# Sheet1.net
KiCad netlist of a schematic drawn in Altium Designer
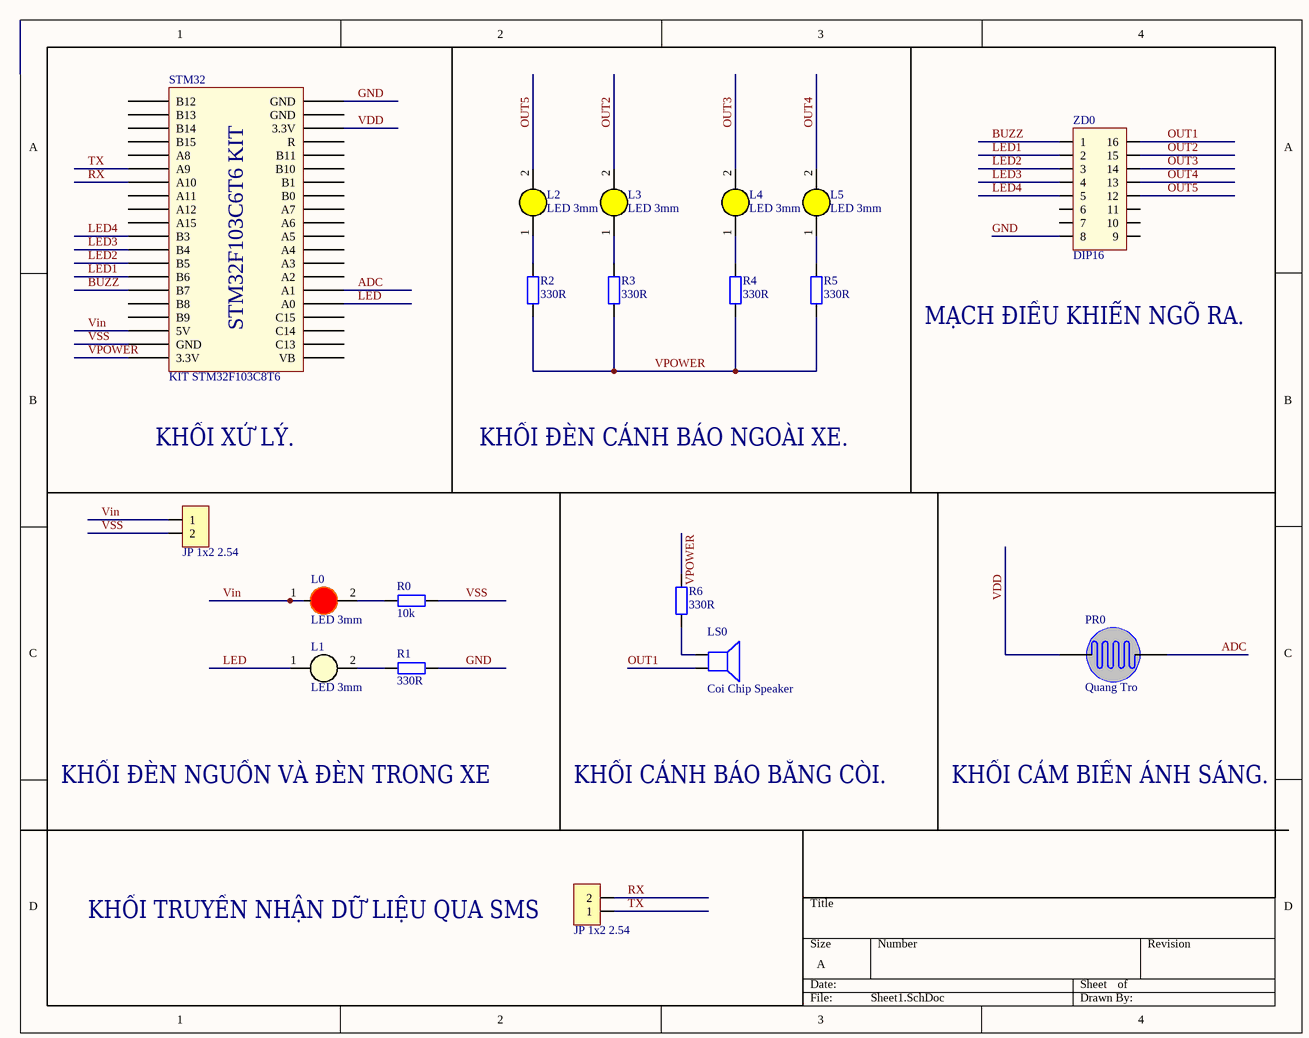
[diagram p0: Sheet1.SchDoc]

(export (version "E")
  (design (tool "Eeschema 10.0.6"))
  (components
    (comp (ref "JP1")
      (value "JP 1x2 2.54")
      (footprint "JP 1x2 DT")
      (description "Cắm")
      (libsource (lib "Altium_Lib_by_KhueNguyenCreator") (part "JP 1x2 2.54 Duc Thang"))
    )
    (comp (ref "JP2")
      (value "JP 1x2 2.54")
      (footprint "JP 1x2 CT")
      (description "Cắm")
      (libsource (lib "Altium_Lib_by_KhueNguyenCreator") (part "JP 1x2 2.54 Cai Thang"))
    )
    (comp (ref "L0")
      (value "LED 3mm")
      (footprint "LED-3MM-RED")
      (description "Cắm")
      (libsource (lib "Altium_Lib_by_KhueNguyenCreator") (part "LED 3mm Do"))
    )
    (comp (ref "L1")
      (value "LED 3mm")
      (footprint "LED-3MM-WHITE")
      (description "Cắm")
      (libsource (lib "Altium_Lib_by_KhueNguyenCreator") (part "LED 3mm Trang"))
    )
    (comp (ref "L2")
      (value "LED 3mm")
      (footprint "LED-3MM-YELLOW")
      (description "Cắm")
      (libsource (lib "Altium_Lib_by_KhueNguyenCreator") (part "LED 3mm Vang"))
    )
    (comp (ref "L3")
      (value "LED 3mm")
      (footprint "LED-3MM-YELLOW")
      (description "Cắm")
      (libsource (lib "Altium_Lib_by_KhueNguyenCreator") (part "LED 3mm Vang"))
    )
    (comp (ref "L4")
      (value "LED 3mm")
      (footprint "LED-3MM-YELLOW")
      (description "Cắm")
      (libsource (lib "Altium_Lib_by_KhueNguyenCreator") (part "LED 3mm Vang"))
    )
    (comp (ref "L5")
      (value "LED 3mm")
      (footprint "LED-3MM-YELLOW")
      (description "Cắm")
      (libsource (lib "Altium_Lib_by_KhueNguyenCreator") (part "LED 3mm Vang"))
    )
    (comp (ref "LS0")
      (value "Coi Chip Speaker")
      (footprint "Coi Chip Speacker")
      (description "Còi chip")
      (libsource (lib "Altium_Lib_by_KhueNguyenCreator") (part "Coi Chip Speaker"))
    )
    (comp (ref "PR0")
      (value "Quang Tro")
      (footprint "Quang Tro")
      (description "Photoresistor")
      (fields (field (name "CREATOR") "Bien Nguyen"))
      (libsource (lib "Altium_Lib_by_KhueNguyenCreator") (part "Quang Tro"))
    )
    (comp (ref "R0")
      (value "10k")
      (footprint "tro vach 1/4w")
      (description "Căm")
      (libsource (lib "Altium_Lib_by_KhueNguyenCreator") (part "Tro Vach 1/4W 5% 10k"))
    )
    (comp (ref "R1")
      (value "330R")
      (footprint "tro vach 1/4w")
      (description "Cắm")
      (libsource (lib "Altium_Lib_by_KhueNguyenCreator") (part "Tro Vach 1/4W 5% 330R"))
    )
    (comp (ref "R2")
      (value "330R")
      (footprint "tro vach 1/4w")
      (description "Cắm")
      (libsource (lib "Altium_Lib_by_KhueNguyenCreator") (part "Tro Vach 1/4W 5% 330R"))
    )
    (comp (ref "R3")
      (value "330R")
      (footprint "tro vach 1/4w")
      (description "Cắm")
      (libsource (lib "Altium_Lib_by_KhueNguyenCreator") (part "Tro Vach 1/4W 5% 330R"))
    )
    (comp (ref "R4")
      (value "330R")
      (footprint "tro vach 1/4w")
      (description "Cắm")
      (libsource (lib "Altium_Lib_by_KhueNguyenCreator") (part "Tro Vach 1/4W 5% 330R"))
    )
    (comp (ref "R5")
      (value "330R")
      (footprint "tro vach 1/4w")
      (description "Cắm")
      (libsource (lib "Altium_Lib_by_KhueNguyenCreator") (part "Tro Vach 1/4W 5% 330R"))
    )
    (comp (ref "R6")
      (value "330R")
      (footprint "tro vach 1/4w")
      (description "Cắm")
      (libsource (lib "Altium_Lib_by_KhueNguyenCreator") (part "Tro Vach 1/4W 5% 330R"))
    )
    (comp (ref "STM32")
      (value "KIT STM32F103C8T6")
      (footprint "STM32F103 KIT")
      (description "KIT STM32F103C8T6 Bluepill")
      (libsource (lib "Altium_Lib_by_KhueNguyenCreator") (part "STM32f103 Bluepill"))
    )
    (comp (ref "ZD0") (value "DIP16") (footprint "DIP16/W0.3") (libsource (lib "syhaunguyen") (part "DIP16")))
  )
  (nets
    (net (code "1") (name "/ADC") (class "Default")
      (node (ref "PR0") (pin "2") (pinfunction "2_2") (pintype "passive"))
      (node (ref "STM32") (pin "26") (pinfunction "A1_26") (pintype "passive"))
    )
    (net (code "2") (name "/BUZZ") (class "Default")
      (node (ref "STM32") (pin "15") (pinfunction "B7_15") (pintype "passive"))
      (node (ref "ZD0") (pin "1") (pinfunction "1_1") (pintype "passive"))
    )
    (net (code "3") (name "/GND") (class "Default")
      (node (ref "R1") (pin "1") (pinfunction "1_1") (pintype "passive"))
      (node (ref "STM32") (pin "40") (pinfunction "GND_40") (pintype "passive"))
      (node (ref "ZD0") (pin "8") (pinfunction "8_8") (pintype "passive"))
    )
    (net (code "4") (name "/LED") (class "Default")
      (node (ref "L1") (pin "1") (pinfunction "A_1") (pintype "passive"))
      (node (ref "STM32") (pin "25") (pinfunction "A0_25") (pintype "passive"))
    )
    (net (code "5") (name "/LED1") (class "Default")
      (node (ref "STM32") (pin "14") (pinfunction "B6_14") (pintype "passive"))
      (node (ref "ZD0") (pin "2") (pinfunction "2_2") (pintype "passive"))
    )
    (net (code "6") (name "/LED2") (class "Default")
      (node (ref "STM32") (pin "13") (pinfunction "B5_13") (pintype "passive"))
      (node (ref "ZD0") (pin "3") (pinfunction "3_3") (pintype "passive"))
    )
    (net (code "7") (name "/LED3") (class "Default")
      (node (ref "STM32") (pin "12") (pinfunction "B4_12") (pintype "passive"))
      (node (ref "ZD0") (pin "4") (pinfunction "4_4") (pintype "passive"))
    )
    (net (code "8") (name "/LED4") (class "Default")
      (node (ref "STM32") (pin "11") (pinfunction "B3_11") (pintype "passive"))
      (node (ref "ZD0") (pin "5") (pinfunction "5_5") (pintype "passive"))
    )
    (net (code "9") (name "/OUT1") (class "Default")
      (node (ref "LS0") (pin "2") (pinfunction "2_2") (pintype "passive"))
      (node (ref "ZD0") (pin "16") (pinfunction "16_16") (pintype "passive"))
    )
    (net (code "10") (name "/OUT2") (class "Default")
      (node (ref "L3") (pin "2") (pinfunction "K_2") (pintype "passive"))
      (node (ref "ZD0") (pin "15") (pinfunction "15_15") (pintype "passive"))
    )
    (net (code "11") (name "/OUT3") (class "Default")
      (node (ref "L4") (pin "2") (pinfunction "K_2") (pintype "passive"))
      (node (ref "ZD0") (pin "14") (pinfunction "14_14") (pintype "passive"))
    )
    (net (code "12") (name "/OUT4") (class "Default")
      (node (ref "L5") (pin "2") (pinfunction "K_2") (pintype "passive"))
      (node (ref "ZD0") (pin "13") (pinfunction "13_13") (pintype "passive"))
    )
    (net (code "13") (name "/OUT5") (class "Default")
      (node (ref "L2") (pin "2") (pinfunction "K_2") (pintype "passive"))
      (node (ref "ZD0") (pin "12") (pinfunction "12_12") (pintype "passive"))
    )
    (net (code "14") (name "/RX") (class "Default")
      (node (ref "JP2") (pin "2") (pinfunction "2_2") (pintype "passive"))
      (node (ref "STM32") (pin "7") (pinfunction "A10_7") (pintype "passive"))
    )
    (net (code "15") (name "/TX") (class "Default")
      (node (ref "JP2") (pin "1") (pinfunction "1_1") (pintype "passive"))
      (node (ref "STM32") (pin "6") (pinfunction "A9_6") (pintype "passive"))
    )
    (net (code "16") (name "/VDD") (class "Default")
      (node (ref "PR0") (pin "1") (pinfunction "1_1") (pintype "passive"))
      (node (ref "STM32") (pin "38") (pinfunction "3.3V_38") (pintype "passive"))
    )
    (net (code "17") (name "/VPOWER") (class "Default")
      (node (ref "R2") (pin "1") (pinfunction "1_1") (pintype "passive"))
      (node (ref "R3") (pin "1") (pinfunction "1_1") (pintype "passive"))
      (node (ref "R4") (pin "1") (pinfunction "1_1") (pintype "passive"))
      (node (ref "R5") (pin "1") (pinfunction "1_1") (pintype "passive"))
      (node (ref "R6") (pin "2") (pinfunction "2_2") (pintype "passive"))
      (node (ref "STM32") (pin "20") (pinfunction "3.3V_20") (pintype "passive"))
    )
    (net (code "18") (name "/VSS") (class "Default")
      (node (ref "JP1") (pin "2") (pinfunction "2_2") (pintype "passive"))
      (node (ref "R0") (pin "2") (pinfunction "2_2") (pintype "passive"))
      (node (ref "STM32") (pin "19") (pinfunction "GND_19") (pintype "passive"))
    )
    (net (code "19") (name "/Vin") (class "Default")
      (node (ref "JP1") (pin "1") (pinfunction "1_1") (pintype "passive"))
      (node (ref "L0") (pin "1") (pinfunction "A_1") (pintype "passive"))
      (node (ref "STM32") (pin "18") (pinfunction "5V_18") (pintype "passive"))
    )
    (net (code "20") (name "Net-(L0-K)") (class "Default")
      (node (ref "L0") (pin "2") (pinfunction "K_2") (pintype "passive"))
      (node (ref "R0") (pin "1") (pinfunction "1_1") (pintype "passive"))
    )
    (net (code "21") (name "Net-(L1-K)") (class "Default")
      (node (ref "L1") (pin "2") (pinfunction "K_2") (pintype "passive"))
      (node (ref "R1") (pin "2") (pinfunction "2_2") (pintype "passive"))
    )
    (net (code "22") (name "Net-(L2-A)") (class "Default")
      (node (ref "L2") (pin "1") (pinfunction "A_1") (pintype "passive"))
      (node (ref "R2") (pin "2") (pinfunction "2_2") (pintype "passive"))
    )
    (net (code "23") (name "Net-(L3-A)") (class "Default")
      (node (ref "L3") (pin "1") (pinfunction "A_1") (pintype "passive"))
      (node (ref "R3") (pin "2") (pinfunction "2_2") (pintype "passive"))
    )
    (net (code "24") (name "Net-(L4-A)") (class "Default")
      (node (ref "L4") (pin "1") (pinfunction "A_1") (pintype "passive"))
      (node (ref "R4") (pin "2") (pinfunction "2_2") (pintype "passive"))
    )
    (net (code "25") (name "Net-(L5-A)") (class "Default")
      (node (ref "L5") (pin "1") (pinfunction "A_1") (pintype "passive"))
      (node (ref "R5") (pin "2") (pinfunction "2_2") (pintype "passive"))
    )
    (net (code "26") (name "Net-(LS0-Pad1)") (class "Default")
      (node (ref "LS0") (pin "1") (pinfunction "1_1") (pintype "passive"))
      (node (ref "R6") (pin "1") (pinfunction "1_1") (pintype "passive"))
    )
    (net (code "27") (name "unconnected-(STM32-A2-Pad27)") (class "Default")
      (node (ref "STM32") (pin "27") (pinfunction "A2_27") (pintype "passive"))
    )
    (net (code "28") (name "unconnected-(STM32-A3-Pad28)") (class "Default")
      (node (ref "STM32") (pin "28") (pinfunction "A3_28") (pintype "passive"))
    )
    (net (code "29") (name "unconnected-(STM32-A4-Pad29)") (class "Default")
      (node (ref "STM32") (pin "29") (pinfunction "A4_29") (pintype "passive"))
    )
    (net (code "30") (name "unconnected-(STM32-A5-Pad30)") (class "Default")
      (node (ref "STM32") (pin "30") (pinfunction "A5_30") (pintype "passive"))
    )
    (net (code "31") (name "unconnected-(STM32-A6-Pad31)") (class "Default")
      (node (ref "STM32") (pin "31") (pinfunction "A6_31") (pintype "passive"))
    )
    (net (code "32") (name "unconnected-(STM32-A7-Pad32)") (class "Default")
      (node (ref "STM32") (pin "32") (pinfunction "A7_32") (pintype "passive"))
    )
    (net (code "33") (name "unconnected-(STM32-A8-Pad5)") (class "Default")
      (node (ref "STM32") (pin "5") (pinfunction "A8_5") (pintype "passive"))
    )
    (net (code "34") (name "unconnected-(STM32-A11-Pad8)") (class "Default")
      (node (ref "STM32") (pin "8") (pinfunction "A11_8") (pintype "passive"))
    )
    (net (code "35") (name "unconnected-(STM32-A12-Pad9)") (class "Default")
      (node (ref "STM32") (pin "9") (pinfunction "A12_9") (pintype "passive"))
    )
    (net (code "36") (name "unconnected-(STM32-A15-Pad10)") (class "Default")
      (node (ref "STM32") (pin "10") (pinfunction "A15_10") (pintype "passive"))
    )
    (net (code "37") (name "unconnected-(STM32-B0-Pad33)") (class "Default")
      (node (ref "STM32") (pin "33") (pinfunction "B0_33") (pintype "passive"))
    )
    (net (code "38") (name "unconnected-(STM32-B1-Pad34)") (class "Default")
      (node (ref "STM32") (pin "34") (pinfunction "B1_34") (pintype "passive"))
    )
    (net (code "39") (name "unconnected-(STM32-B8-Pad16)") (class "Default")
      (node (ref "STM32") (pin "16") (pinfunction "B8_16") (pintype "passive"))
    )
    (net (code "40") (name "unconnected-(STM32-B9-Pad17)") (class "Default")
      (node (ref "STM32") (pin "17") (pinfunction "B9_17") (pintype "passive"))
    )
    (net (code "41") (name "unconnected-(STM32-B10-Pad35)") (class "Default")
      (node (ref "STM32") (pin "35") (pinfunction "B10_35") (pintype "passive"))
    )
    (net (code "42") (name "unconnected-(STM32-B11-Pad36)") (class "Default")
      (node (ref "STM32") (pin "36") (pinfunction "B11_36") (pintype "passive"))
    )
    (net (code "43") (name "unconnected-(STM32-B12-Pad1)") (class "Default")
      (node (ref "STM32") (pin "1") (pinfunction "B12_1") (pintype "passive"))
    )
    (net (code "44") (name "unconnected-(STM32-B13-Pad2)") (class "Default")
      (node (ref "STM32") (pin "2") (pinfunction "B13_2") (pintype "passive"))
    )
    (net (code "45") (name "unconnected-(STM32-B14-Pad3)") (class "Default")
      (node (ref "STM32") (pin "3") (pinfunction "B14_3") (pintype "passive"))
    )
    (net (code "46") (name "unconnected-(STM32-B15-Pad4)") (class "Default")
      (node (ref "STM32") (pin "4") (pinfunction "B15_4") (pintype "passive"))
    )
    (net (code "47") (name "unconnected-(STM32-C13-Pad22)") (class "Default")
      (node (ref "STM32") (pin "22") (pinfunction "C13_22") (pintype "passive"))
    )
    (net (code "48") (name "unconnected-(STM32-C14-Pad23)") (class "Default")
      (node (ref "STM32") (pin "23") (pinfunction "C14_23") (pintype "passive"))
    )
    (net (code "49") (name "unconnected-(STM32-C15-Pad24)") (class "Default")
      (node (ref "STM32") (pin "24") (pinfunction "C15_24") (pintype "passive"))
    )
    (net (code "50") (name "unconnected-(STM32-GND-Pad39)") (class "Default")
      (node (ref "STM32") (pin "39") (pinfunction "GND_39") (pintype "passive"))
    )
    (net (code "51") (name "unconnected-(STM32-R-Pad37)") (class "Default")
      (node (ref "STM32") (pin "37") (pinfunction "R_37") (pintype "passive"))
    )
    (net (code "52") (name "unconnected-(STM32-VB-Pad21)") (class "Default")
      (node (ref "STM32") (pin "21") (pinfunction "VB_21") (pintype "passive"))
    )
    (net (code "53") (name "unconnected-(ZD0-Pad6)") (class "Default")
      (node (ref "ZD0") (pin "6") (pinfunction "6_6") (pintype "passive"))
    )
    (net (code "54") (name "unconnected-(ZD0-Pad7)") (class "Default")
      (node (ref "ZD0") (pin "7") (pinfunction "7_7") (pintype "passive"))
    )
    (net (code "55") (name "unconnected-(ZD0-Pad9)") (class "Default")
      (node (ref "ZD0") (pin "9") (pinfunction "9_9") (pintype "passive"))
    )
    (net (code "56") (name "unconnected-(ZD0-Pad10)") (class "Default")
      (node (ref "ZD0") (pin "10") (pinfunction "10_10") (pintype "passive"))
    )
    (net (code "57") (name "unconnected-(ZD0-Pad11)") (class "Default")
      (node (ref "ZD0") (pin "11") (pinfunction "11_11") (pintype "passive"))
    )
  )
)
